# aw_301_runner.net
KiCad netlist of a schematic drawn in EAGLE
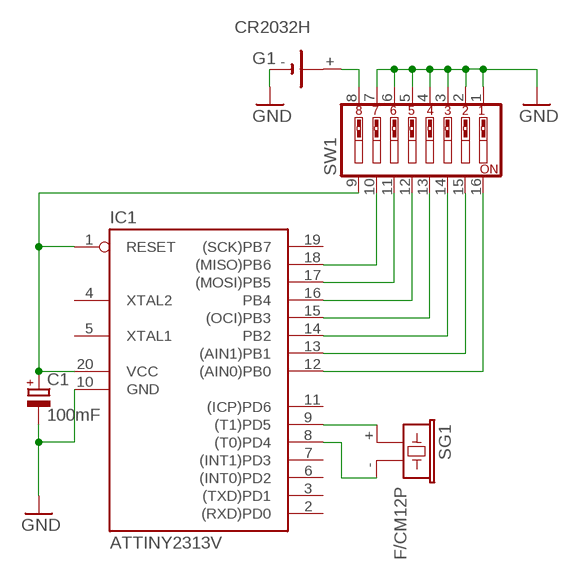
[diagram p0: schematic, sheet 1]

(export (version "E")
  (design (tool "Eeschema 10.0.6"))
  (components
    (comp (ref "C1")
      (value "100mF")
      (footprint "eagle-import:E2,5-6")
      (libsource (lib "eagle-import") (part "CPOL-EUE2.5-6"))
    )
    (comp (ref "G1")
      (value "CR2032H")
      (footprint "eagle-import:CR2032H")
      (libsource (lib "eagle-import") (part "CR2032H"))
    )
    (comp (ref "IC1")
      (value "ATTINY2313V")
      (footprint "eagle-import:DIL20")
      (libsource (lib "eagle-import") (part "AT90S2313P"))
    )
    (comp (ref "SG1")
      (value "F/CM12P")
      (footprint "eagle-import:F_CM12P")
      (libsource (lib "eagle-import") (part "F/CM12P"))
    )
    (comp (ref "SW1")
      (value "SW_DIP-8")
      (footprint "eagle-import:EDG-08")
      (libsource (lib "eagle-import") (part "SW_DIP-8"))
    )
  )
  (nets
    (net (code "1") (name "GND") (class "Default")
      (node (ref "C1") (pin "-") (pinfunction "-_-") (pintype "passive"))
      (node (ref "G1") (pin "-") (pinfunction "-_-") (pintype "passive"))
      (node (ref "IC1") (pin "10") (pinfunction "GND_10") (pintype "power_in"))
      (node (ref "SW1") (pin "1") (pinfunction "1_1") (pintype "passive"))
      (node (ref "SW1") (pin "2") (pinfunction "2_2") (pintype "passive"))
      (node (ref "SW1") (pin "3") (pinfunction "3_3") (pintype "passive"))
      (node (ref "SW1") (pin "4") (pinfunction "4_4") (pintype "passive"))
      (node (ref "SW1") (pin "5") (pinfunction "5_5") (pintype "passive"))
      (node (ref "SW1") (pin "6") (pinfunction "6_6") (pintype "passive"))
      (node (ref "SW1") (pin "7") (pinfunction "7_7") (pintype "passive"))
    )
    (net (code "2") (name "Net-(G1-Pad+)") (class "Default")
      (node (ref "G1") (pin "+") (pinfunction "+_+") (pintype "passive"))
      (node (ref "SW1") (pin "8") (pinfunction "8_8") (pintype "passive"))
    )
    (net (code "3") (name "Net-(IC1-(AIN0)PB0)") (class "Default")
      (node (ref "IC1") (pin "12") (pinfunction "(AIN0)PB0_12") (pintype "bidirectional"))
      (node (ref "SW1") (pin "16") (pinfunction "16_16") (pintype "passive"))
    )
    (net (code "4") (name "Net-(IC1-(AIN1)PB1)") (class "Default")
      (node (ref "IC1") (pin "13") (pinfunction "(AIN1)PB1_13") (pintype "bidirectional"))
      (node (ref "SW1") (pin "15") (pinfunction "15_15") (pintype "passive"))
    )
    (net (code "5") (name "Net-(IC1-(MISO)PB6)") (class "Default")
      (node (ref "IC1") (pin "18") (pinfunction "(MISO)PB6_18") (pintype "bidirectional"))
      (node (ref "SW1") (pin "10") (pinfunction "10_10") (pintype "passive"))
    )
    (net (code "6") (name "Net-(IC1-(MOSI)PB5)") (class "Default")
      (node (ref "IC1") (pin "17") (pinfunction "(MOSI)PB5_17") (pintype "bidirectional"))
      (node (ref "SW1") (pin "11") (pinfunction "11_11") (pintype "passive"))
    )
    (net (code "7") (name "Net-(IC1-(OCI)PB3)") (class "Default")
      (node (ref "IC1") (pin "15") (pinfunction "(OCI)PB3_15") (pintype "bidirectional"))
      (node (ref "SW1") (pin "13") (pinfunction "13_13") (pintype "passive"))
    )
    (net (code "8") (name "Net-(IC1-(T0)PD4)") (class "Default")
      (node (ref "IC1") (pin "8") (pinfunction "(T0)PD4_8") (pintype "bidirectional"))
      (node (ref "SG1") (pin "-") (pinfunction "2_-") (pintype "passive"))
    )
    (net (code "9") (name "Net-(IC1-(T1)PD5)") (class "Default")
      (node (ref "IC1") (pin "9") (pinfunction "(T1)PD5_9") (pintype "bidirectional"))
      (node (ref "SG1") (pin "+") (pinfunction "1_+") (pintype "passive"))
    )
    (net (code "10") (name "Net-(IC1-PB2)") (class "Default")
      (node (ref "IC1") (pin "14") (pinfunction "PB2_14") (pintype "bidirectional"))
      (node (ref "SW1") (pin "14") (pinfunction "14_14") (pintype "passive"))
    )
    (net (code "11") (name "Net-(IC1-PB4)") (class "Default")
      (node (ref "IC1") (pin "16") (pinfunction "PB4_16") (pintype "bidirectional"))
      (node (ref "SW1") (pin "12") (pinfunction "12_12") (pintype "passive"))
    )
    (net (code "12") (name "Net-(IC1-RESET)") (class "Default")
      (node (ref "C1") (pin "+") (pinfunction "+_+") (pintype "passive"))
      (node (ref "IC1") (pin "1") (pinfunction "RESET_1") (pintype "bidirectional"))
      (node (ref "IC1") (pin "20") (pinfunction "VCC_20") (pintype "power_in"))
      (node (ref "SW1") (pin "9") (pinfunction "9_9") (pintype "passive"))
    )
    (net (code "13") (name "unconnected-(G1-+-Pad+@1)") (class "Default")
      (node (ref "G1") (pin "+@1") (pinfunction "+_+@1") (pintype "passive"))
    )
    (net (code "14") (name "unconnected-(IC1-(ICP)PD6-Pad11)") (class "Default")
      (node (ref "IC1") (pin "11") (pinfunction "(ICP)PD6_11") (pintype "bidirectional"))
    )
    (net (code "15") (name "unconnected-(IC1-(INT0)PD2-Pad6)") (class "Default")
      (node (ref "IC1") (pin "6") (pinfunction "(INT0)PD2_6") (pintype "bidirectional"))
    )
    (net (code "16") (name "unconnected-(IC1-(INT1)PD3-Pad7)") (class "Default")
      (node (ref "IC1") (pin "7") (pinfunction "(INT1)PD3_7") (pintype "bidirectional"))
    )
    (net (code "17") (name "unconnected-(IC1-(RXD)PD0-Pad2)") (class "Default")
      (node (ref "IC1") (pin "2") (pinfunction "(RXD)PD0_2") (pintype "bidirectional"))
    )
    (net (code "18") (name "unconnected-(IC1-(SCK)PB7-Pad19)") (class "Default")
      (node (ref "IC1") (pin "19") (pinfunction "(SCK)PB7_19") (pintype "bidirectional"))
    )
    (net (code "19") (name "unconnected-(IC1-(TXD)PD1-Pad3)") (class "Default")
      (node (ref "IC1") (pin "3") (pinfunction "(TXD)PD1_3") (pintype "bidirectional"))
    )
    (net (code "20") (name "unconnected-(IC1-XTAL1-Pad5)") (class "Default")
      (node (ref "IC1") (pin "5") (pinfunction "XTAL1_5") (pintype "bidirectional"))
    )
    (net (code "21") (name "unconnected-(IC1-XTAL2-Pad4)") (class "Default")
      (node (ref "IC1") (pin "4") (pinfunction "XTAL2_4") (pintype "bidirectional"))
    )
  )
)
